# MaESP_ESP32-C3_1_3_OLED_V1_1.net
KiCad netlist of a schematic drawn in EAGLE
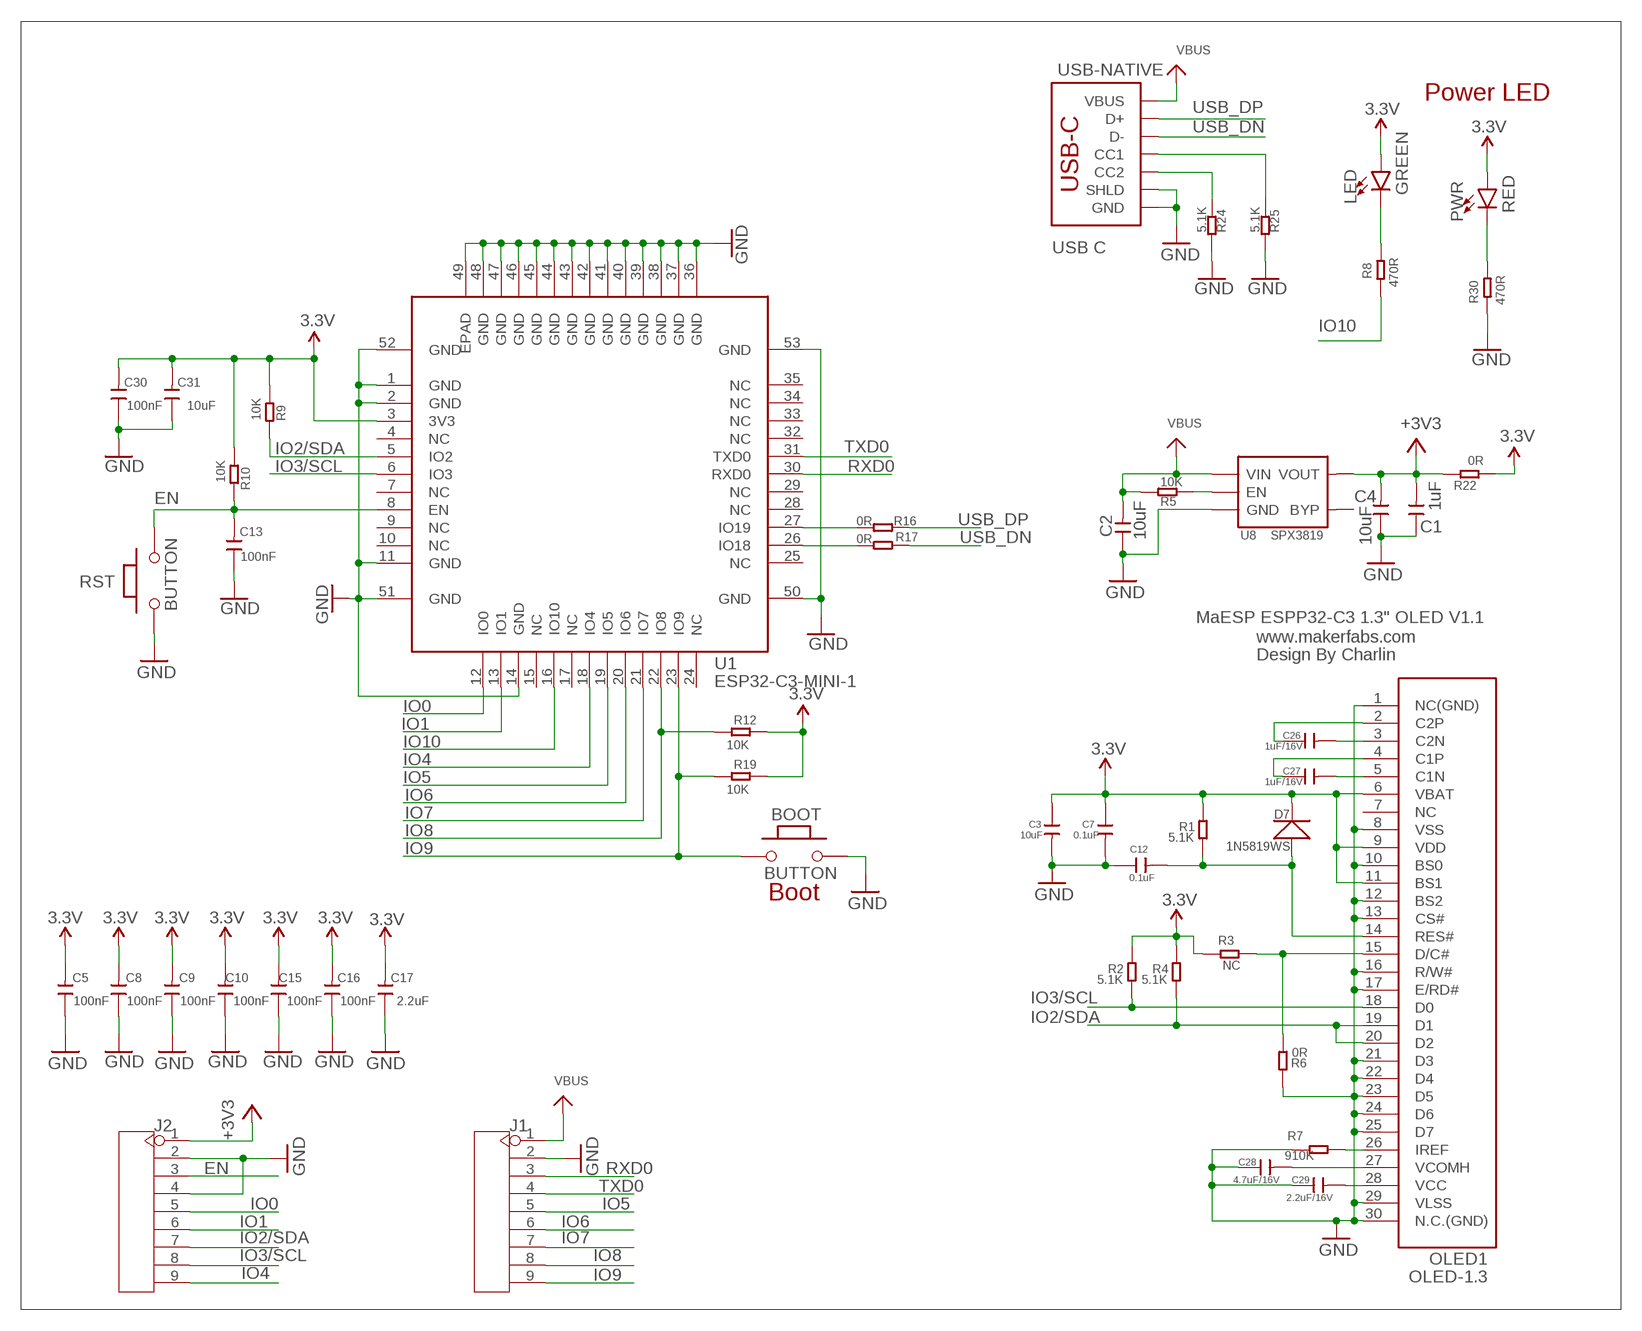
[diagram p0: schematic, sheet 1]

(export (version "E")
  (design (tool "Eeschema 10.0.6"))
  (components
    (comp (ref "BOOT")
      (value "BUTTON")
      (footprint "eagle-import:157SW")
      (libsource (lib "eagle-import") (part "PB157"))
    )
    (comp (ref "C1")
      (value "1uF")
      (footprint "eagle-import:C0603")
      (libsource (lib "eagle-import") (part "C-0603"))
    )
    (comp (ref "C2")
      (value "10uF")
      (footprint "eagle-import:C0603")
      (libsource (lib "eagle-import") (part "C-0603"))
    )
    (comp (ref "C3")
      (value "10uF")
      (footprint "eagle-import:C0603")
      (libsource (lib "eagle-import") (part "C-0603"))
    )
    (comp (ref "C4")
      (value "10uF")
      (footprint "eagle-import:C0603")
      (libsource (lib "eagle-import") (part "C-0603"))
    )
    (comp (ref "C5")
      (value "100nF")
      (footprint "eagle-import:C0603")
      (libsource (lib "eagle-import") (part "C-0603"))
    )
    (comp (ref "C7")
      (value "0.1uF")
      (footprint "eagle-import:C0603")
      (libsource (lib "eagle-import") (part "C-0603"))
    )
    (comp (ref "C8")
      (value "100nF")
      (footprint "eagle-import:C0603")
      (libsource (lib "eagle-import") (part "C-0603"))
    )
    (comp (ref "C9")
      (value "100nF")
      (footprint "eagle-import:C0603")
      (libsource (lib "eagle-import") (part "C-0603"))
    )
    (comp (ref "C10")
      (value "100nF")
      (footprint "eagle-import:C0603")
      (libsource (lib "eagle-import") (part "C-0603"))
    )
    (comp (ref "C12")
      (value "0.1uF")
      (footprint "eagle-import:C0603")
      (libsource (lib "eagle-import") (part "C-0603"))
    )
    (comp (ref "C13")
      (value "100nF")
      (footprint "eagle-import:C0603")
      (libsource (lib "eagle-import") (part "C-0603"))
    )
    (comp (ref "C15")
      (value "100nF")
      (footprint "eagle-import:C0603")
      (libsource (lib "eagle-import") (part "C-0603"))
    )
    (comp (ref "C16")
      (value "100nF")
      (footprint "eagle-import:C0603")
      (libsource (lib "eagle-import") (part "C-0603"))
    )
    (comp (ref "C17")
      (value "2.2uF")
      (footprint "eagle-import:C0603")
      (libsource (lib "eagle-import") (part "C-0603"))
    )
    (comp (ref "C26")
      (value "1uF/16V")
      (footprint "eagle-import:C0603")
      (libsource (lib "eagle-import") (part "C-0603"))
    )
    (comp (ref "C27")
      (value "1uF/16V")
      (footprint "eagle-import:C0603")
      (libsource (lib "eagle-import") (part "C-0603"))
    )
    (comp (ref "C28")
      (value "4.7uF/16V")
      (footprint "eagle-import:C0603")
      (libsource (lib "eagle-import") (part "C-0603"))
    )
    (comp (ref "C29")
      (value "2.2uF/16V")
      (footprint "eagle-import:C0603")
      (libsource (lib "eagle-import") (part "C-0603"))
    )
    (comp (ref "C30")
      (value "100nF")
      (footprint "eagle-import:C0603")
      (libsource (lib "eagle-import") (part "C-0603"))
    )
    (comp (ref "C31")
      (value "10uF")
      (footprint "eagle-import:C0603")
      (libsource (lib "eagle-import") (part "C-0603"))
    )
    (comp (ref "D7")
      (value "1N5819WS")
      (footprint "eagle-import:SOD323")
      (libsource (lib "eagle-import") (part "D'0805'"))
    )
    (comp (ref "J1")
      (value "HEADER-9P-2.54")
      (footprint "eagle-import:9P-2.54")
      (libsource (lib "eagle-import") (part "HEADER-9P-2.54"))
    )
    (comp (ref "J2")
      (value "HEADER-9P-2.54")
      (footprint "eagle-import:9P-2.54")
      (libsource (lib "eagle-import") (part "HEADER-9P-2.54"))
    )
    (comp (ref "LED")
      (value "GREEN")
      (footprint "eagle-import:LED-0603")
      (libsource (lib "eagle-import") (part "LED-RED0603"))
    )
    (comp (ref "OLED1")
      (value "OLED-1.3")
      (footprint "eagle-import:OLED-1.3")
      (libsource (lib "eagle-import") (part "OLED-1.3"))
    )
    (comp (ref "PWR")
      (value "RED")
      (footprint "eagle-import:LED-0603")
      (libsource (lib "eagle-import") (part "LED-RED0603"))
    )
    (comp (ref "R1")
      (value "5.1K")
      (footprint "eagle-import:R0603")
      (libsource (lib "eagle-import") (part "R-0603"))
    )
    (comp (ref "R2")
      (value "5.1K")
      (footprint "eagle-import:R0603")
      (libsource (lib "eagle-import") (part "R-0603"))
    )
    (comp (ref "R3")
      (value "NC")
      (footprint "eagle-import:R0603")
      (libsource (lib "eagle-import") (part "R-0603"))
    )
    (comp (ref "R4")
      (value "5.1K")
      (footprint "eagle-import:R0603")
      (libsource (lib "eagle-import") (part "R-0603"))
    )
    (comp (ref "R5")
      (value "10K")
      (footprint "eagle-import:R0603")
      (libsource (lib "eagle-import") (part "R-0603"))
    )
    (comp (ref "R6")
      (value "0R")
      (footprint "eagle-import:R0603")
      (libsource (lib "eagle-import") (part "R-0603"))
    )
    (comp (ref "R7")
      (value "910K")
      (footprint "eagle-import:R0603")
      (libsource (lib "eagle-import") (part "R-0603"))
    )
    (comp (ref "R8")
      (value "470R")
      (footprint "eagle-import:R0603")
      (libsource (lib "eagle-import") (part "R-0603"))
    )
    (comp (ref "R9")
      (value "10K")
      (footprint "eagle-import:R0603")
      (libsource (lib "eagle-import") (part "R-0603"))
    )
    (comp (ref "R10")
      (value "10K")
      (footprint "eagle-import:R0603")
      (libsource (lib "eagle-import") (part "R-0603"))
    )
    (comp (ref "R12")
      (value "10K")
      (footprint "eagle-import:R0603")
      (libsource (lib "eagle-import") (part "R-0603"))
    )
    (comp (ref "R16")
      (value "0R")
      (footprint "eagle-import:R0603")
      (libsource (lib "eagle-import") (part "R-0603"))
    )
    (comp (ref "R17")
      (value "0R")
      (footprint "eagle-import:R0603")
      (libsource (lib "eagle-import") (part "R-0603"))
    )
    (comp (ref "R19")
      (value "10K")
      (footprint "eagle-import:R0603")
      (libsource (lib "eagle-import") (part "R-0603"))
    )
    (comp (ref "R22")
      (value "0R")
      (footprint "eagle-import:R0603")
      (libsource (lib "eagle-import") (part "R-0603"))
    )
    (comp (ref "R24")
      (value "5.1K")
      (footprint "eagle-import:R0603")
      (libsource (lib "eagle-import") (part "R-0603"))
    )
    (comp (ref "R25")
      (value "5.1K")
      (footprint "eagle-import:R0603")
      (libsource (lib "eagle-import") (part "R-0603"))
    )
    (comp (ref "R30")
      (value "470R")
      (footprint "eagle-import:R0603")
      (libsource (lib "eagle-import") (part "R-0603"))
    )
    (comp (ref "RST")
      (value "BUTTON")
      (footprint "eagle-import:157SW")
      (libsource (lib "eagle-import") (part "PB157"))
    )
    (comp (ref "U1")
      (value "ESP32-C3-MINI-1")
      (footprint "eagle-import:ESP32-C3-MINI-1")
      (libsource (lib "eagle-import") (part "ESP32-C3-MINI-1"))
    )
    (comp (ref "U8")
      (value "SPX3819")
      (footprint "eagle-import:SOT23-5")
      (libsource (lib "eagle-import") (part "SPX3819"))
    )
    (comp (ref "USB-NATIVE")
      (value "USB C")
      (footprint "eagle-import:USB-C-16P-4LAYER-ISOLATED")
      (libsource (lib "eagle-import") (part "USB_C_4-LAYER-ISOLATED"))
    )
  )
  (nets
    (net (code "1") (name "+3V3") (class "Default")
      (node (ref "C1") (pin "2") (pinfunction "2_2") (pintype "passive"))
      (node (ref "C4") (pin "2") (pinfunction "2_2") (pintype "passive"))
      (node (ref "J2") (pin "1") (pinfunction "1_1") (pintype "bidirectional"))
      (node (ref "R22") (pin "2") (pinfunction "2_2") (pintype "passive"))
      (node (ref "U8") (pin "5") (pinfunction "VOUT_5") (pintype "bidirectional"))
    )
    (net (code "2") (name "/EN") (class "Default")
      (node (ref "C13") (pin "2") (pinfunction "2_2") (pintype "passive"))
      (node (ref "J2") (pin "3") (pinfunction "3_3") (pintype "bidirectional"))
      (node (ref "R10") (pin "2") (pinfunction "2_2") (pintype "passive"))
      (node (ref "RST") (pin "2") (pinfunction "2_2") (pintype "passive"))
      (node (ref "U1") (pin "8") (pinfunction "EN_8") (pintype "bidirectional"))
    )
    (net (code "3") (name "/IO0") (class "Default")
      (node (ref "J2") (pin "5") (pinfunction "5_5") (pintype "bidirectional"))
      (node (ref "U1") (pin "12") (pinfunction "IO0_12") (pintype "bidirectional"))
    )
    (net (code "4") (name "/IO1") (class "Default")
      (node (ref "J2") (pin "6") (pinfunction "6_6") (pintype "bidirectional"))
      (node (ref "U1") (pin "13") (pinfunction "IO1_13") (pintype "bidirectional"))
    )
    (net (code "5") (name "/IO2{slash}SDA") (class "Default")
      (node (ref "J2") (pin "7") (pinfunction "7_7") (pintype "bidirectional"))
      (node (ref "OLED1") (pin "19") (pinfunction "D1_19") (pintype "bidirectional"))
      (node (ref "OLED1") (pin "20") (pinfunction "D2_20") (pintype "bidirectional"))
      (node (ref "R4") (pin "1") (pinfunction "1_1") (pintype "passive"))
      (node (ref "R9") (pin "2") (pinfunction "2_2") (pintype "passive"))
      (node (ref "U1") (pin "5") (pinfunction "IO2_5") (pintype "bidirectional"))
    )
    (net (code "6") (name "/IO3{slash}SCL") (class "Default")
      (node (ref "J2") (pin "8") (pinfunction "8_8") (pintype "bidirectional"))
      (node (ref "OLED1") (pin "18") (pinfunction "D0_18") (pintype "bidirectional"))
      (node (ref "R2") (pin "1") (pinfunction "1_1") (pintype "passive"))
      (node (ref "U1") (pin "6") (pinfunction "IO3_6") (pintype "bidirectional"))
    )
    (net (code "7") (name "/IO4") (class "Default")
      (node (ref "J2") (pin "9") (pinfunction "9_9") (pintype "bidirectional"))
      (node (ref "U1") (pin "18") (pinfunction "IO4_18") (pintype "bidirectional"))
    )
    (net (code "8") (name "/IO5") (class "Default")
      (node (ref "J1") (pin "5") (pinfunction "5_5") (pintype "bidirectional"))
      (node (ref "U1") (pin "19") (pinfunction "IO5_19") (pintype "bidirectional"))
    )
    (net (code "9") (name "/IO6") (class "Default")
      (node (ref "J1") (pin "6") (pinfunction "6_6") (pintype "bidirectional"))
      (node (ref "U1") (pin "20") (pinfunction "IO6_20") (pintype "bidirectional"))
    )
    (net (code "10") (name "/IO7") (class "Default")
      (node (ref "J1") (pin "7") (pinfunction "7_7") (pintype "bidirectional"))
      (node (ref "U1") (pin "21") (pinfunction "IO7_21") (pintype "bidirectional"))
    )
    (net (code "11") (name "/IO8") (class "Default")
      (node (ref "J1") (pin "8") (pinfunction "8_8") (pintype "bidirectional"))
      (node (ref "R12") (pin "1") (pinfunction "1_1") (pintype "passive"))
      (node (ref "U1") (pin "22") (pinfunction "IO8_22") (pintype "bidirectional"))
    )
    (net (code "12") (name "/IO9") (class "Default")
      (node (ref "BOOT") (pin "1") (pinfunction "1_1") (pintype "passive"))
      (node (ref "J1") (pin "9") (pinfunction "9_9") (pintype "bidirectional"))
      (node (ref "R19") (pin "1") (pinfunction "1_1") (pintype "passive"))
      (node (ref "U1") (pin "23") (pinfunction "IO9_23") (pintype "bidirectional"))
    )
    (net (code "13") (name "/IO10") (class "Default")
      (node (ref "R8") (pin "2") (pinfunction "2_2") (pintype "passive"))
      (node (ref "U1") (pin "16") (pinfunction "IO10_16") (pintype "bidirectional"))
    )
    (net (code "14") (name "/RXD0") (class "Default")
      (node (ref "J1") (pin "3") (pinfunction "3_3") (pintype "bidirectional"))
      (node (ref "U1") (pin "30") (pinfunction "RXD0_30") (pintype "bidirectional"))
    )
    (net (code "15") (name "/TXD0") (class "Default")
      (node (ref "J1") (pin "4") (pinfunction "4_4") (pintype "bidirectional"))
      (node (ref "U1") (pin "31") (pinfunction "TXD0_31") (pintype "bidirectional"))
    )
    (net (code "16") (name "/USB_DN") (class "Default")
      (node (ref "R17") (pin "2") (pinfunction "2_2") (pintype "passive"))
      (node (ref "USB-NATIVE") (pin "A7") (pinfunction "D-_A7") (pintype "bidirectional"))
      (node (ref "USB-NATIVE") (pin "B7") (pinfunction "D-_B7") (pintype "bidirectional"))
    )
    (net (code "17") (name "/USB_DP") (class "Default")
      (node (ref "R16") (pin "2") (pinfunction "2_2") (pintype "passive"))
      (node (ref "USB-NATIVE") (pin "A6") (pinfunction "D+_A6") (pintype "bidirectional"))
      (node (ref "USB-NATIVE") (pin "B6") (pinfunction "D+_B6") (pintype "bidirectional"))
    )
    (net (code "18") (name "3.3V") (class "Default")
      (node (ref "C10") (pin "2") (pinfunction "2_2") (pintype "passive"))
      (node (ref "C15") (pin "2") (pinfunction "2_2") (pintype "passive"))
      (node (ref "C16") (pin "2") (pinfunction "2_2") (pintype "passive"))
      (node (ref "C17") (pin "2") (pinfunction "2_2") (pintype "passive"))
      (node (ref "C3") (pin "1") (pinfunction "1_1") (pintype "passive"))
      (node (ref "C30") (pin "2") (pinfunction "2_2") (pintype "passive"))
      (node (ref "C31") (pin "2") (pinfunction "2_2") (pintype "passive"))
      (node (ref "C5") (pin "2") (pinfunction "2_2") (pintype "passive"))
      (node (ref "C7") (pin "1") (pinfunction "1_1") (pintype "passive"))
      (node (ref "C8") (pin "2") (pinfunction "2_2") (pintype "passive"))
      (node (ref "C9") (pin "2") (pinfunction "2_2") (pintype "passive"))
      (node (ref "D7") (pin "-") (pinfunction "-_-") (pintype "passive"))
      (node (ref "LED") (pin "A") (pinfunction "A_A") (pintype "passive"))
      (node (ref "OLED1") (pin "11") (pinfunction "BS1_11") (pintype "bidirectional"))
      (node (ref "OLED1") (pin "6") (pinfunction "VBAT_6") (pintype "bidirectional"))
      (node (ref "OLED1") (pin "9") (pinfunction "VDD_9") (pintype "bidirectional"))
      (node (ref "PWR") (pin "A") (pinfunction "A_A") (pintype "passive"))
      (node (ref "R1") (pin "2") (pinfunction "2_2") (pintype "passive"))
      (node (ref "R10") (pin "1") (pinfunction "1_1") (pintype "passive"))
      (node (ref "R12") (pin "2") (pinfunction "2_2") (pintype "passive"))
      (node (ref "R19") (pin "2") (pinfunction "2_2") (pintype "passive"))
      (node (ref "R2") (pin "2") (pinfunction "2_2") (pintype "passive"))
      (node (ref "R22") (pin "1") (pinfunction "1_1") (pintype "passive"))
      (node (ref "R3") (pin "2") (pinfunction "2_2") (pintype "passive"))
      (node (ref "R4") (pin "2") (pinfunction "2_2") (pintype "passive"))
      (node (ref "R9") (pin "1") (pinfunction "1_1") (pintype "passive"))
      (node (ref "U1") (pin "3") (pinfunction "3V3_3") (pintype "bidirectional"))
    )
    (net (code "19") (name "GND") (class "Default")
      (node (ref "BOOT") (pin "2") (pinfunction "2_2") (pintype "passive"))
      (node (ref "C1") (pin "1") (pinfunction "1_1") (pintype "passive"))
      (node (ref "C10") (pin "1") (pinfunction "1_1") (pintype "passive"))
      (node (ref "C12") (pin "1") (pinfunction "1_1") (pintype "passive"))
      (node (ref "C13") (pin "1") (pinfunction "1_1") (pintype "passive"))
      (node (ref "C15") (pin "1") (pinfunction "1_1") (pintype "passive"))
      (node (ref "C16") (pin "1") (pinfunction "1_1") (pintype "passive"))
      (node (ref "C17") (pin "1") (pinfunction "1_1") (pintype "passive"))
      (node (ref "C2") (pin "1") (pinfunction "1_1") (pintype "passive"))
      (node (ref "C28") (pin "1") (pinfunction "1_1") (pintype "passive"))
      (node (ref "C29") (pin "1") (pinfunction "1_1") (pintype "passive"))
      (node (ref "C3") (pin "2") (pinfunction "2_2") (pintype "passive"))
      (node (ref "C30") (pin "1") (pinfunction "1_1") (pintype "passive"))
      (node (ref "C31") (pin "1") (pinfunction "1_1") (pintype "passive"))
      (node (ref "C4") (pin "1") (pinfunction "1_1") (pintype "passive"))
      (node (ref "C5") (pin "1") (pinfunction "1_1") (pintype "passive"))
      (node (ref "C7") (pin "2") (pinfunction "2_2") (pintype "passive"))
      (node (ref "C8") (pin "1") (pinfunction "1_1") (pintype "passive"))
      (node (ref "C9") (pin "1") (pinfunction "1_1") (pintype "passive"))
      (node (ref "J1") (pin "2") (pinfunction "2_2") (pintype "bidirectional"))
      (node (ref "J2") (pin "2") (pinfunction "2_2") (pintype "bidirectional"))
      (node (ref "J2") (pin "4") (pinfunction "4_4") (pintype "bidirectional"))
      (node (ref "OLED1") (pin "1") (pinfunction "NC(GND)_1") (pintype "bidirectional"))
      (node (ref "OLED1") (pin "10") (pinfunction "BS0_10") (pintype "bidirectional"))
      (node (ref "OLED1") (pin "12") (pinfunction "BS2_12") (pintype "bidirectional"))
      (node (ref "OLED1") (pin "13") (pinfunction "CS#_13") (pintype "bidirectional"))
      (node (ref "OLED1") (pin "16") (pinfunction "R/W#_16") (pintype "bidirectional"))
      (node (ref "OLED1") (pin "17") (pinfunction "E/RD#_17") (pintype "bidirectional"))
      (node (ref "OLED1") (pin "21") (pinfunction "D3_21") (pintype "bidirectional"))
      (node (ref "OLED1") (pin "22") (pinfunction "D4_22") (pintype "bidirectional"))
      (node (ref "OLED1") (pin "23") (pinfunction "D5_23") (pintype "bidirectional"))
      (node (ref "OLED1") (pin "24") (pinfunction "D6_24") (pintype "bidirectional"))
      (node (ref "OLED1") (pin "25") (pinfunction "D7_25") (pintype "bidirectional"))
      (node (ref "OLED1") (pin "29") (pinfunction "VLSS_29") (pintype "bidirectional"))
      (node (ref "OLED1") (pin "30") (pinfunction "N.C.(GND)_30") (pintype "bidirectional"))
      (node (ref "OLED1") (pin "8") (pinfunction "VSS_8") (pintype "bidirectional"))
      (node (ref "R24") (pin "1") (pinfunction "1_1") (pintype "passive"))
      (node (ref "R25") (pin "1") (pinfunction "1_1") (pintype "passive"))
      (node (ref "R30") (pin "2") (pinfunction "2_2") (pintype "passive"))
      (node (ref "R6") (pin "2") (pinfunction "2_2") (pintype "passive"))
      (node (ref "R7") (pin "2") (pinfunction "2_2") (pintype "passive"))
      (node (ref "RST") (pin "1") (pinfunction "1_1") (pintype "passive"))
      (node (ref "U1") (pin "1") (pinfunction "GND_1") (pintype "bidirectional"))
      (node (ref "U1") (pin "11") (pinfunction "GND_11") (pintype "bidirectional"))
      (node (ref "U1") (pin "14") (pinfunction "GND_14") (pintype "bidirectional"))
      (node (ref "U1") (pin "2") (pinfunction "GND_2") (pintype "bidirectional"))
      (node (ref "U1") (pin "36") (pinfunction "GND_36") (pintype "bidirectional"))
      (node (ref "U1") (pin "37") (pinfunction "GND_37") (pintype "bidirectional"))
      (node (ref "U1") (pin "38") (pinfunction "GND_38") (pintype "bidirectional"))
      (node (ref "U1") (pin "39") (pinfunction "GND_39") (pintype "bidirectional"))
      (node (ref "U1") (pin "40") (pinfunction "GND_40") (pintype "bidirectional"))
      (node (ref "U1") (pin "41") (pinfunction "GND_41") (pintype "bidirectional"))
      (node (ref "U1") (pin "42") (pinfunction "GND_42") (pintype "bidirectional"))
      (node (ref "U1") (pin "43") (pinfunction "GND_43") (pintype "bidirectional"))
      (node (ref "U1") (pin "44") (pinfunction "GND_44") (pintype "bidirectional"))
      (node (ref "U1") (pin "45") (pinfunction "GND_45") (pintype "bidirectional"))
      (node (ref "U1") (pin "46") (pinfunction "GND_46") (pintype "bidirectional"))
      (node (ref "U1") (pin "47") (pinfunction "GND_47") (pintype "bidirectional"))
      (node (ref "U1") (pin "48") (pinfunction "GND_48") (pintype "bidirectional"))
      (node (ref "U1") (pin "49") (pinfunction "EPAD_49") (pintype "bidirectional"))
      (node (ref "U1") (pin "50") (pinfunction "GND_50") (pintype "bidirectional"))
      (node (ref "U1") (pin "51") (pinfunction "GND_51") (pintype "bidirectional"))
      (node (ref "U1") (pin "52") (pinfunction "GND_52") (pintype "bidirectional"))
      (node (ref "U1") (pin "53") (pinfunction "GND_53") (pintype "bidirectional"))
      (node (ref "U8") (pin "2") (pinfunction "GND_2") (pintype "bidirectional"))
      (node (ref "USB-NATIVE") (pin "GND") (pinfunction "GND_GND") (pintype "bidirectional"))
      (node (ref "USB-NATIVE") (pin "GND2") (pinfunction "GND_GND2") (pintype "bidirectional"))
      (node (ref "USB-NATIVE") (pin "SHLD1") (pinfunction "SHLD_SHLD1") (pintype "bidirectional"))
      (node (ref "USB-NATIVE") (pin "SHLD2") (pinfunction "SHLD_SHLD2") (pintype "bidirectional"))
      (node (ref "USB-NATIVE") (pin "SHLD3") (pinfunction "SHLD_SHLD3") (pintype "bidirectional"))
      (node (ref "USB-NATIVE") (pin "SHLD4") (pinfunction "SHLD_SHLD4") (pintype "bidirectional"))
      (node (ref "USB-NATIVE") (pin "SHLD5") (pinfunction "SHLD_SHLD5") (pintype "bidirectional"))
      (node (ref "USB-NATIVE") (pin "SHLD6") (pinfunction "SHLD_SHLD6") (pintype "bidirectional"))
      (node (ref "USB-NATIVE") (pin "SHLD7") (pinfunction "SHLD_SHLD7") (pintype "bidirectional"))
      (node (ref "USB-NATIVE") (pin "SHLD8") (pinfunction "SHLD_SHLD8") (pintype "bidirectional"))
    )
    (net (code "20") (name "Net-(LED-PadC)") (class "Default")
      (node (ref "LED") (pin "C") (pinfunction "C_C") (pintype "passive"))
      (node (ref "R8") (pin "1") (pinfunction "1_1") (pintype "passive"))
    )
    (net (code "21") (name "Net-(OLED1-C1N)") (class "Default")
      (node (ref "C27") (pin "2") (pinfunction "2_2") (pintype "passive"))
      (node (ref "OLED1") (pin "5") (pinfunction "C1N_5") (pintype "bidirectional"))
    )
    (net (code "22") (name "Net-(OLED1-C1P)") (class "Default")
      (node (ref "C27") (pin "1") (pinfunction "1_1") (pintype "passive"))
      (node (ref "OLED1") (pin "4") (pinfunction "C1P_4") (pintype "bidirectional"))
    )
    (net (code "23") (name "Net-(OLED1-C2N)") (class "Default")
      (node (ref "C26") (pin "2") (pinfunction "2_2") (pintype "passive"))
      (node (ref "OLED1") (pin "3") (pinfunction "C2N_3") (pintype "bidirectional"))
    )
    (net (code "24") (name "Net-(OLED1-C2P)") (class "Default")
      (node (ref "C26") (pin "1") (pinfunction "1_1") (pintype "passive"))
      (node (ref "OLED1") (pin "2") (pinfunction "C2P_2") (pintype "bidirectional"))
    )
    (net (code "25") (name "Net-(OLED1-D{slash}C#)") (class "Default")
      (node (ref "OLED1") (pin "15") (pinfunction "D/C#_15") (pintype "bidirectional"))
      (node (ref "R3") (pin "1") (pinfunction "1_1") (pintype "passive"))
      (node (ref "R6") (pin "1") (pinfunction "1_1") (pintype "passive"))
    )
    (net (code "26") (name "Net-(OLED1-IREF)") (class "Default")
      (node (ref "OLED1") (pin "26") (pinfunction "IREF_26") (pintype "bidirectional"))
      (node (ref "R7") (pin "1") (pinfunction "1_1") (pintype "passive"))
    )
    (net (code "27") (name "Net-(OLED1-RES#)") (class "Default")
      (node (ref "C12") (pin "2") (pinfunction "2_2") (pintype "passive"))
      (node (ref "D7") (pin "+") (pinfunction "+_+") (pintype "passive"))
      (node (ref "OLED1") (pin "14") (pinfunction "RES#_14") (pintype "bidirectional"))
      (node (ref "R1") (pin "1") (pinfunction "1_1") (pintype "passive"))
    )
    (net (code "28") (name "Net-(OLED1-VCC)") (class "Default")
      (node (ref "C29") (pin "2") (pinfunction "2_2") (pintype "passive"))
      (node (ref "OLED1") (pin "28") (pinfunction "VCC_28") (pintype "bidirectional"))
    )
    (net (code "29") (name "Net-(OLED1-VCOMH)") (class "Default")
      (node (ref "C28") (pin "2") (pinfunction "2_2") (pintype "passive"))
      (node (ref "OLED1") (pin "27") (pinfunction "VCOMH_27") (pintype "bidirectional"))
    )
    (net (code "30") (name "Net-(PWR-PadC)") (class "Default")
      (node (ref "PWR") (pin "C") (pinfunction "C_C") (pintype "passive"))
      (node (ref "R30") (pin "1") (pinfunction "1_1") (pintype "passive"))
    )
    (net (code "31") (name "Net-(U1-IO18)") (class "Default")
      (node (ref "R17") (pin "1") (pinfunction "1_1") (pintype "passive"))
      (node (ref "U1") (pin "26") (pinfunction "IO18_26") (pintype "bidirectional"))
    )
    (net (code "32") (name "Net-(U1-IO19)") (class "Default")
      (node (ref "R16") (pin "1") (pinfunction "1_1") (pintype "passive"))
      (node (ref "U1") (pin "27") (pinfunction "IO19_27") (pintype "bidirectional"))
    )
    (net (code "33") (name "Net-(U8-EN)") (class "Default")
      (node (ref "R5") (pin "2") (pinfunction "2_2") (pintype "passive"))
      (node (ref "U8") (pin "3") (pinfunction "EN_3") (pintype "bidirectional"))
    )
    (net (code "34") (name "Net-(USB-NATIVE-CC1)") (class "Default")
      (node (ref "R25") (pin "2") (pinfunction "2_2") (pintype "passive"))
      (node (ref "USB-NATIVE") (pin "A5") (pinfunction "CC1_A5") (pintype "bidirectional"))
    )
    (net (code "35") (name "Net-(USB-NATIVE-CC2)") (class "Default")
      (node (ref "R24") (pin "2") (pinfunction "2_2") (pintype "passive"))
      (node (ref "USB-NATIVE") (pin "B5") (pinfunction "CC2_B5") (pintype "bidirectional"))
    )
    (net (code "36") (name "VBUS") (class "Default")
      (node (ref "C2") (pin "2") (pinfunction "2_2") (pintype "passive"))
      (node (ref "J1") (pin "1") (pinfunction "1_1") (pintype "bidirectional"))
      (node (ref "R5") (pin "1") (pinfunction "1_1") (pintype "passive"))
      (node (ref "U8") (pin "1") (pinfunction "VIN_1") (pintype "bidirectional"))
      (node (ref "USB-NATIVE") (pin "VBUS1") (pinfunction "VBUS_VBUS1") (pintype "bidirectional"))
      (node (ref "USB-NATIVE") (pin "VBUS2") (pinfunction "VBUS_VBUS2") (pintype "bidirectional"))
    )
    (net (code "37") (name "unconnected-(OLED1-NC-Pad7)") (class "Default")
      (node (ref "OLED1") (pin "7") (pinfunction "NC_7") (pintype "bidirectional"))
    )
    (net (code "38") (name "unconnected-(U1-NC-Pad4)") (class "Default")
      (node (ref "U1") (pin "4") (pinfunction "NC_4") (pintype "bidirectional"))
    )
    (net (code "39") (name "unconnected-(U1-NC-Pad7)") (class "Default")
      (node (ref "U1") (pin "7") (pinfunction "NC_7") (pintype "bidirectional"))
    )
    (net (code "40") (name "unconnected-(U1-NC-Pad9)") (class "Default")
      (node (ref "U1") (pin "9") (pinfunction "NC_9") (pintype "bidirectional"))
    )
    (net (code "41") (name "unconnected-(U1-NC-Pad10)") (class "Default")
      (node (ref "U1") (pin "10") (pinfunction "NC_10") (pintype "bidirectional"))
    )
    (net (code "42") (name "unconnected-(U1-NC-Pad15)") (class "Default")
      (node (ref "U1") (pin "15") (pinfunction "NC_15") (pintype "bidirectional"))
    )
    (net (code "43") (name "unconnected-(U1-NC-Pad17)") (class "Default")
      (node (ref "U1") (pin "17") (pinfunction "NC_17") (pintype "bidirectional"))
    )
    (net (code "44") (name "unconnected-(U1-NC-Pad24)") (class "Default")
      (node (ref "U1") (pin "24") (pinfunction "NC_24") (pintype "bidirectional"))
    )
    (net (code "45") (name "unconnected-(U1-NC-Pad25)") (class "Default")
      (node (ref "U1") (pin "25") (pinfunction "NC_25") (pintype "bidirectional"))
    )
    (net (code "46") (name "unconnected-(U1-NC-Pad28)") (class "Default")
      (node (ref "U1") (pin "28") (pinfunction "NC_28") (pintype "bidirectional"))
    )
    (net (code "47") (name "unconnected-(U1-NC-Pad29)") (class "Default")
      (node (ref "U1") (pin "29") (pinfunction "NC_29") (pintype "bidirectional"))
    )
    (net (code "48") (name "unconnected-(U1-NC-Pad32)") (class "Default")
      (node (ref "U1") (pin "32") (pinfunction "NC_32") (pintype "bidirectional"))
    )
    (net (code "49") (name "unconnected-(U1-NC-Pad33)") (class "Default")
      (node (ref "U1") (pin "33") (pinfunction "NC_33") (pintype "bidirectional"))
    )
    (net (code "50") (name "unconnected-(U1-NC-Pad34)") (class "Default")
      (node (ref "U1") (pin "34") (pinfunction "NC_34") (pintype "bidirectional"))
    )
    (net (code "51") (name "unconnected-(U1-NC-Pad35)") (class "Default")
      (node (ref "U1") (pin "35") (pinfunction "NC_35") (pintype "bidirectional"))
    )
    (net (code "52") (name "unconnected-(U8-BYP-Pad4)") (class "Default")
      (node (ref "U8") (pin "4") (pinfunction "BYP_4") (pintype "bidirectional"))
    )
  )
)
